# Power.net
KiCad netlist of a schematic drawn in Altium Designer
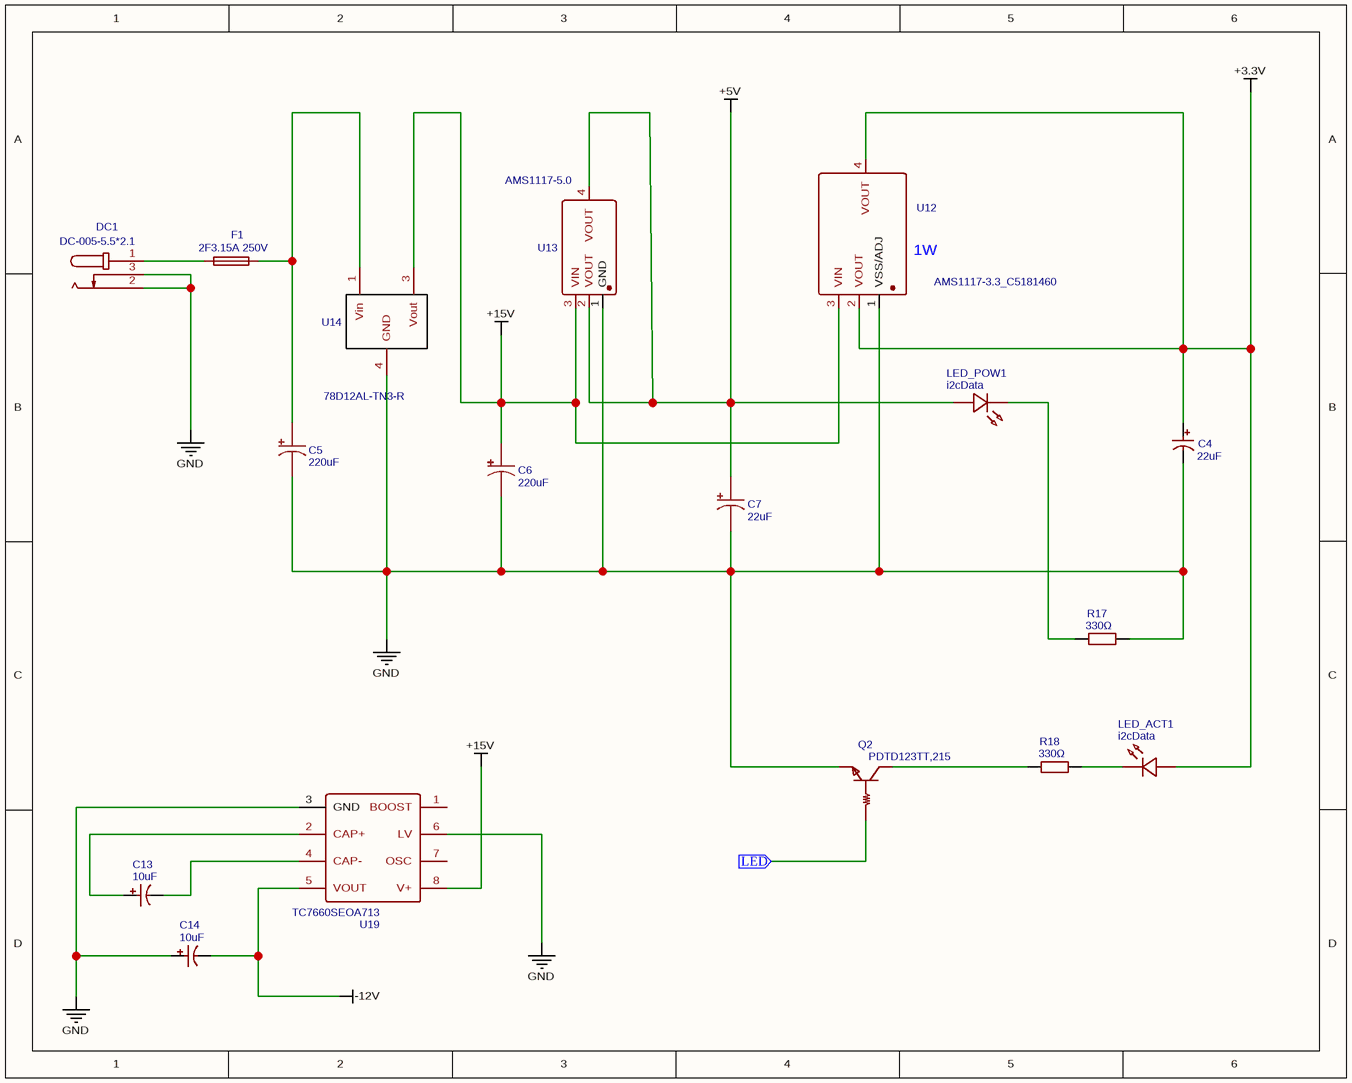
[diagram p0: Power.schdoc]

(export (version "E")
  (design (tool "Eeschema 10.0.6"))
  (components
    (comp (ref "C4")
      (value "22uF")
      (fields (field (name "MANUFACTURER") "ROQANG(容强)") (field (name "MANUFACTURER PART") "RVE1C220M0405"))
      (libsource (lib "altium-import") (part "root_3_22uF_"))
    )
    (comp (ref "C5")
      (value "220uF")
      (fields
        (field (name "MANUFACTURER") "Nichicon(尼吉康)")
        (field (name "MANUFACTURER PART") "UWT1H221MNL1GS")
        (field (name "CONTRIBUTOR") "LCSC")
      )
      (libsource (lib "altium-import") (part "root_0_220uF_"))
    )
    (comp (ref "C6")
      (value "220uF")
      (fields
        (field (name "MANUFACTURER") "Nichicon(尼吉康)")
        (field (name "MANUFACTURER PART") "UWT1H221MNL1GS")
        (field (name "CONTRIBUTOR") "LCSC")
      )
      (libsource (lib "altium-import") (part "root_0_220uF_"))
    )
    (comp (ref "C7")
      (value "22uF")
      (fields
        (field (name "MANUFACTURER") "ROQANG")
        (field (name "MANUFACTURER PART") "VT1E220M0505")
        (field (name "CONTRIBUTOR") "LCSC")
      )
      (libsource (lib "altium-import") (part "root_0_22uF_"))
    )
    (comp (ref "C13")
      (value "10uF")
      (fields
        (field (name "MANUFACTURER") "CX(承兴)")
        (field (name "MANUFACTURER PART") "KS106M025C07RR0VH2FP0")
      )
      (libsource (lib "altium-import") (part "root_0_10uF_"))
    )
    (comp (ref "C14")
      (value "10uF")
      (fields
        (field (name "MANUFACTURER") "CX(承兴)")
        (field (name "MANUFACTURER PART") "KS106M025C07RR0VH2FP0")
      )
      (libsource (lib "altium-import") (part "root_0_10uF_"))
    )
    (comp (ref "DC1")
      (value "DC-005-5.5*2.1")
      (fields (field (name "CONTRIBUTOR") "lcsc"))
      (libsource (lib "altium-import") (part "root_0_DC-005-5.5*2.1_"))
    )
    (comp (ref "F1")
      (value "2F3.15A 250V")
      (fields
        (field (name "MANUFACTURER") "xcfuse(旭程)")
        (field (name "MANUFACTURER PART") "2F.3150212000R1B02")
        (field (name "CONTRIBUTOR") "LCSC")
      )
      (libsource (lib "altium-import") (part "root_0_2F3.15A 250V_"))
    )
    (comp (ref "LED_ACT1")
      (value "i2cData")
      (fields
        (field (name "MANUFACTURER") "TUOZHAN(拓展光电)")
        (field (name "MANUFACTURER PART") "TZ-L2-03YYBYG1GDJ30-001")
        (field (name "CONTRIBUTOR") "LCSC")
      )
      (libsource (lib "altium-import") (part "root_0_i2cData_"))
    )
    (comp (ref "LED_POW1")
      (value "i2cData")
      (fields
        (field (name "MANUFACTURER") "TUOZHAN(拓展光电)")
        (field (name "MANUFACTURER PART") "TZ-L2-03YYBYG1GDJ30-001")
        (field (name "CONTRIBUTOR") "LCSC")
      )
      (libsource (lib "altium-import") (part "root_2_i2cData_"))
    )
    (comp (ref "Q2")
      (value "PDTD123TT,215")
      (fields (field (name "MANUFACTURER") "Nexperia(安世)") (field (name "CONTRIBUTOR") "LCSC"))
      (libsource (lib "altium-import") (part "root_1_PDTD123TT,215_"))
    )
    (comp (ref "R17")
      (value "330Ω")
      (fields
        (field (name "MANUFACTURER") "FH")
        (field (name "MANUFACTURER PART") "RS-03K331FT")
        (field (name "CONTRIBUTOR") "LCSC")
      )
      (libsource (lib "altium-import") (part "root_0_330Ω_"))
    )
    (comp (ref "R18")
      (value "330Ω")
      (fields
        (field (name "MANUFACTURER") "FH")
        (field (name "MANUFACTURER PART") "RS-03K331FT")
        (field (name "CONTRIBUTOR") "LCSC")
      )
      (libsource (lib "altium-import") (part "root_0_330Ω_"))
    )
    (comp (ref "U12")
      (value "AMS1117-3.3_C5181460")
      (fields
        (field (name "MANUFACTURER") "HX(恒佳兴)")
        (field (name "MANUFACTURER PART") "AMS1117-3.3")
        (field (name "CONTRIBUTOR") "lcsc")
      )
      (libsource (lib "altium-import") (part "root_0_AMS1117-3.3_C5181460_"))
    )
    (comp (ref "U13")
      (value "AMS1117-5.0")
      (fields (field (name "MANUFACTURER") "AMS"))
      (libsource (lib "altium-import") (part "root_1_AMS1117-5.0_"))
    )
    (comp (ref "U14")
      (value "78D12AL-TN3-R")
      (fields (field (name "MANUFACTURER") "UTC(友顺)"))
      (libsource (lib "altium-import") (part "root_1_78D12AL-TN3-R_"))
    )
    (comp (ref "U19")
      (value "TC7660SEOA713")
      (fields (field (name "MANUFACTURER") "MICROCHIP(美国微芯)") (field (name "CONTRIBUTOR") "LCSC"))
      (libsource (lib "altium-import") (part "root_0_TC7660SEOA713_"))
    )
  )
  (nets
    (net (code "1") (name "+3.3V") (class "Default")
      (node (ref "C4") (pin "1") (pinfunction "1_1") (pintype "passive"))
      (node (ref "LED_ACT1") (pin "2") (pinfunction "A_2") (pintype "passive"))
      (node (ref "U12") (pin "2") (pinfunction "VOUT_2") (pintype "passive"))
      (node (ref "U12") (pin "4") (pinfunction "VOUT_4") (pintype "passive"))
    )
    (net (code "2") (name "+5V") (class "Default")
      (node (ref "C7") (pin "1") (pinfunction "1_1") (pintype "passive"))
      (node (ref "LED_POW1") (pin "2") (pinfunction "A_2") (pintype "passive"))
      (node (ref "U13") (pin "2") (pinfunction "VOUT_2") (pintype "passive"))
      (node (ref "U13") (pin "4") (pinfunction "VOUT_4") (pintype "passive"))
    )
    (net (code "3") (name "+15V") (class "Default")
      (node (ref "C6") (pin "1") (pinfunction "1_1") (pintype "passive"))
      (node (ref "U12") (pin "3") (pinfunction "VIN_3") (pintype "passive"))
      (node (ref "U13") (pin "3") (pinfunction "VIN_3") (pintype "passive"))
      (node (ref "U14") (pin "3") (pinfunction "Vout_3") (pintype "passive"))
      (node (ref "U19") (pin "8") (pinfunction "V+_8") (pintype "passive"))
    )
    (net (code "4") (name "-12V") (class "Default")
      (node (ref "C14") (pin "2") (pinfunction "2_2") (pintype "passive"))
      (node (ref "U19") (pin "5") (pinfunction "VOUT_5") (pintype "passive"))
    )
    (net (code "5") (name "/LED") (class "Default")
      (node (ref "Q2") (pin "1") (pinfunction "B_1") (pintype "passive"))
    )
    (net (code "6") (name "GND") (class "Default")
      (node (ref "C14") (pin "1") (pinfunction "1_1") (pintype "passive"))
      (node (ref "C4") (pin "2") (pinfunction "2_2") (pintype "passive"))
      (node (ref "C5") (pin "2") (pinfunction "2_2") (pintype "passive"))
      (node (ref "C6") (pin "2") (pinfunction "2_2") (pintype "passive"))
      (node (ref "C7") (pin "2") (pinfunction "2_2") (pintype "passive"))
      (node (ref "DC1") (pin "2") (pinfunction "2_2") (pintype "passive"))
      (node (ref "DC1") (pin "3") (pinfunction "3_3") (pintype "passive"))
      (node (ref "Q2") (pin "2") (pinfunction "E_2") (pintype "passive"))
      (node (ref "R17") (pin "2") (pinfunction "2_2") (pintype "passive"))
      (node (ref "U12") (pin "1") (pinfunction "VSS/ADJ_1") (pintype "passive"))
      (node (ref "U13") (pin "1") (pinfunction "GND_1") (pintype "passive"))
      (node (ref "U14") (pin "4") (pinfunction "GND_4") (pintype "passive"))
      (node (ref "U19") (pin "3") (pinfunction "GND_3") (pintype "passive"))
      (node (ref "U19") (pin "6") (pinfunction "LV_6") (pintype "passive"))
    )
    (net (code "7") (name "Net-(DC1-Pad1)") (class "Default")
      (node (ref "DC1") (pin "1") (pinfunction "1_1") (pintype "passive"))
      (node (ref "F1") (pin "1") (pinfunction "1_1") (pintype "passive"))
    )
    (net (code "8") (name "Net-(LED_ACT1-K)") (class "Default")
      (node (ref "LED_ACT1") (pin "1") (pinfunction "K_1") (pintype "passive"))
      (node (ref "R18") (pin "2") (pinfunction "2_2") (pintype "passive"))
    )
    (net (code "9") (name "Net-(LED_POW1-K)") (class "Default")
      (node (ref "LED_POW1") (pin "1") (pinfunction "K_1") (pintype "passive"))
      (node (ref "R17") (pin "1") (pinfunction "1_1") (pintype "passive"))
    )
    (net (code "10") (name "Net-(Q2-C)") (class "Default")
      (node (ref "Q2") (pin "3") (pinfunction "C_3") (pintype "passive"))
      (node (ref "R18") (pin "1") (pinfunction "1_1") (pintype "passive"))
    )
    (net (code "11") (name "Net-(U14-Vin)") (class "Default")
      (node (ref "C5") (pin "1") (pinfunction "1_1") (pintype "passive"))
      (node (ref "F1") (pin "2") (pinfunction "2_2") (pintype "passive"))
      (node (ref "U14") (pin "1") (pinfunction "Vin_1") (pintype "passive"))
    )
    (net (code "12") (name "Net-(U19-CAP+)") (class "Default")
      (node (ref "C13") (pin "1") (pinfunction "1_1") (pintype "passive"))
      (node (ref "U19") (pin "2") (pinfunction "CAP+_2") (pintype "passive"))
    )
    (net (code "13") (name "Net-(U19-CAP-)") (class "Default")
      (node (ref "C13") (pin "2") (pinfunction "2_2") (pintype "passive"))
      (node (ref "U19") (pin "4") (pinfunction "CAP-_4") (pintype "passive"))
    )
    (net (code "14") (name "unconnected-(U19-BOOST-Pad1)") (class "Default")
      (node (ref "U19") (pin "1") (pinfunction "BOOST_1") (pintype "passive"))
    )
    (net (code "15") (name "unconnected-(U19-OSC-Pad7)") (class "Default")
      (node (ref "U19") (pin "7") (pinfunction "OSC_7") (pintype "passive"))
    )
  )
)
